# Sheet4.net
KiCad netlist of a schematic drawn in Altium Designer
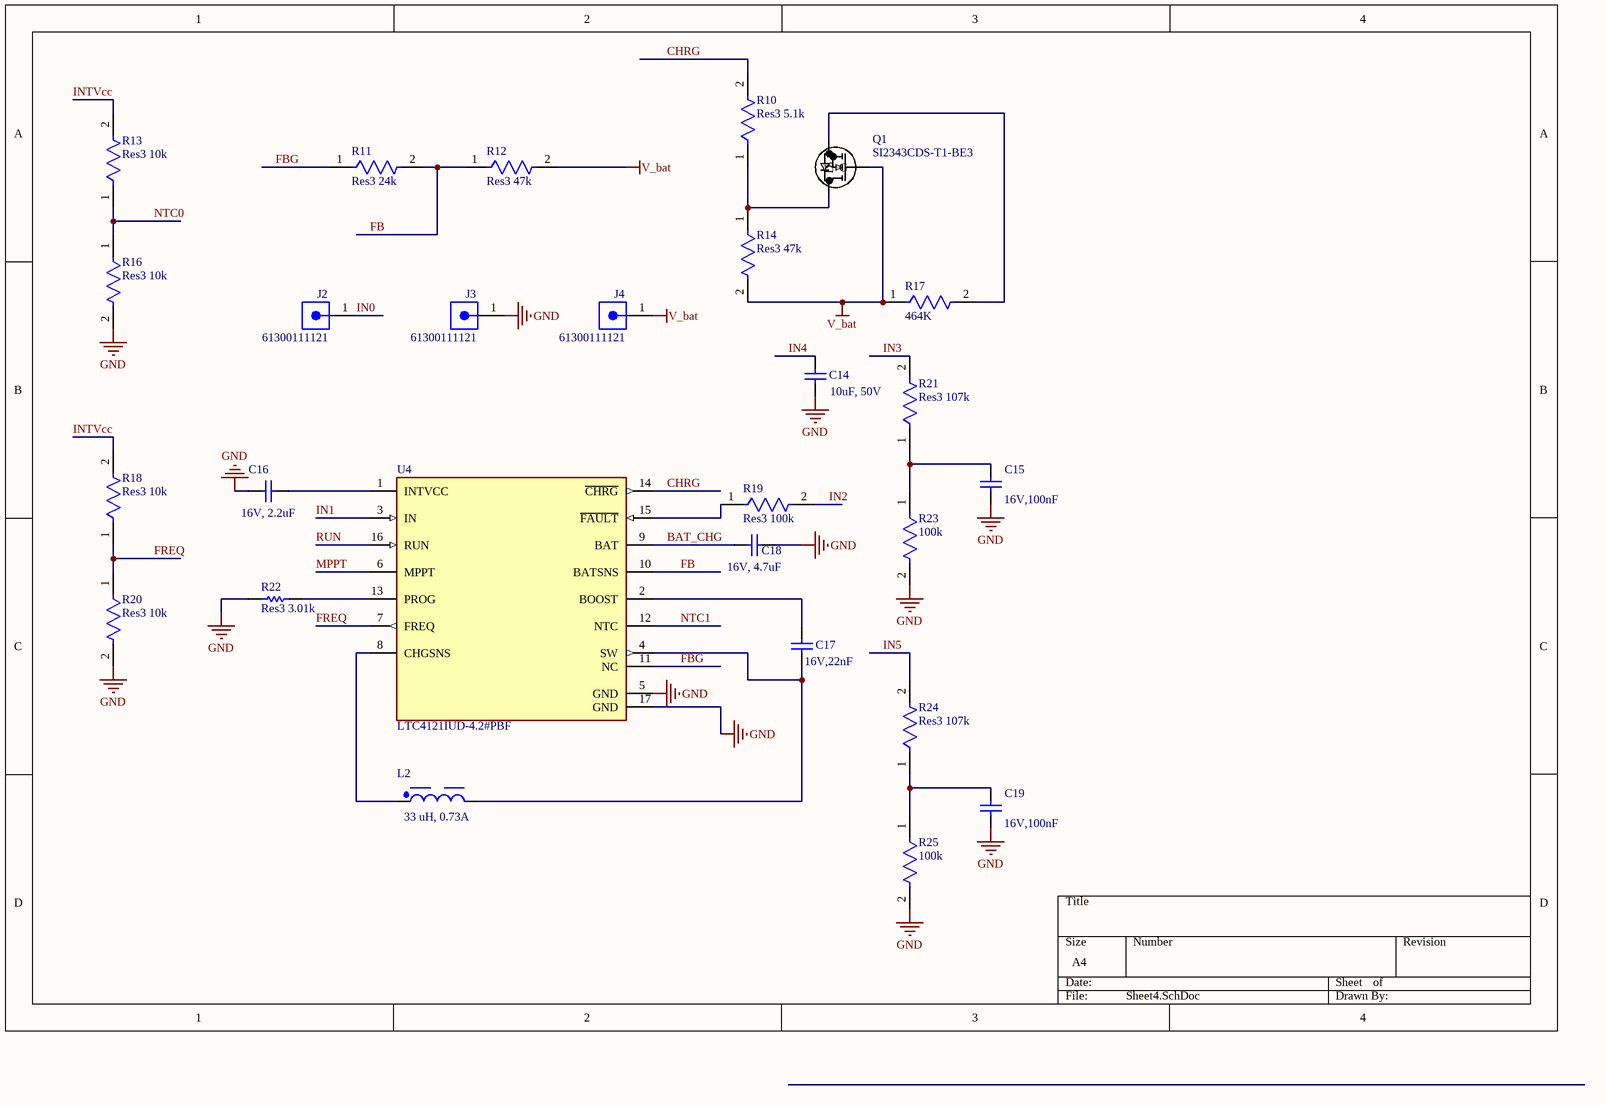
[diagram p0: Sheet4.SchDoc]

(export (version "E")
  (design (tool "Eeschema 10.0.6"))
  (components
    (comp (ref "C14")
      (value "10uF, 50V")
      (footprint "WCAP-CSGP_1206_L3.2W1.6H1.6")
      (description "Cap, 10Uf, 50V, Mlcc, 1206 Rohs Compliant: Yes")
      (libsource (lib "Altium Content Vault") (part "Capacitor_Non-Polarized"))
    )
    (comp (ref "C15")
      (value "16V,100nF")
      (footprint "WCAP-CSGP_0603_L1.6W0.8H0.8_Reflow")
      (description "Cap Ceramic 0.1uF 16V X7R 10% Pad SMD 0603 125C T/R")
      (fields (field (name "TOLERANCE") "10%"))
      (libsource (lib "Altium Content Vault") (part "Capacitor_Non-Polarized"))
    )
    (comp (ref "C16")
      (value "16V, 2.2uF")
      (footprint "WCAP-CSGP_0603_L1.6W0.8H0.8_Reflow")
      (description "Cap Ceramic 2.2uF 16V X5R 20% Pad SMD 0603 85C T/R")
      (fields (field (name "TOLERANCE") "20%"))
      (libsource (lib "Altium Content Vault") (part "Capacitor_Non-Polarized"))
    )
    (comp (ref "C17")
      (value "16V,22nF")
      (footprint "WCAP-CSGP_0603_L1.6W0.8H0.8_Reflow")
      (description "Cap Ceramic 0.022uF 16V X7R 10% Pad SMD 0603 125C T/R")
      (fields (field (name "TOLERANCE") "10%"))
      (libsource (lib "Altium Content Vault") (part "Capacitor_Non-Polarized"))
    )
    (comp (ref "C18")
      (value "16V, 4.7uF")
      (footprint "WCAP-CSGP_0805_L2W1.25H1.25")
      (description "Multilayer Ceramic Capacitor 4.7uF 0805")
      (fields (field (name "TOLERANCE") "20%"))
      (libsource (lib "Altium Content Vault") (part "Capacitor_Non-Polarized"))
    )
    (comp (ref "C19")
      (value "16V,100nF")
      (footprint "WCAP-CSGP_0603_L1.6W0.8H0.8_Reflow")
      (description "Cap Ceramic 0.1uF 16V X7R 10% Pad SMD 0603 125C T/R")
      (fields (field (name "TOLERANCE") "10%"))
      (libsource (lib "Altium Content Vault") (part "Capacitor_Non-Polarized"))
    )
    (comp (ref "J2")
      (value "61300111121")
      (footprint "61300111121")
      (description "THT Vertical Pin Header WR-PHD, Pitch 2.54 mm, Single Row, 1 pins")
      (libsource (lib "Altium Content Vault") (part "Header_Male_1R_01P"))
    )
    (comp (ref "J3")
      (value "61300111121")
      (footprint "61300111121")
      (description "THT Vertical Pin Header WR-PHD, Pitch 2.54 mm, Single Row, 1 pins")
      (libsource (lib "Altium Content Vault") (part "Header_Male_1R_01P"))
    )
    (comp (ref "J4")
      (value "61300111121")
      (footprint "61300111121")
      (description "THT Vertical Pin Header WR-PHD, Pitch 2.54 mm, Single Row, 1 pins")
      (libsource (lib "Altium Content Vault") (part "Header_Male_1R_01P"))
    )
    (comp (ref "L2")
      (value "33 uH, 0.73A")
      (footprint "WE-TPC_4818")
      (description "WE-TPC SMT Shielded Tiny Power Inductor")
      (libsource (lib "Altium Content Vault") (part "Inductor - 2"))
    )
    (comp (ref "Q1")
      (value "SI2343CDS-T1-BE3")
      (footprint "SOT-23_TO-236_VIS")
      (description "P-CHANNEL 30-V (D-S) MOSFET")
      (fields (field (name "COPYRIGHT") "Copyright (C) 2026 Ultra Librarian. All rights reserved."))
      (libsource (lib "Schlib1") (part "SI2343CDS-T1-BE3"))
    )
    (comp (ref "R10")
      (value "Res3 5.1k")
      (footprint "FP-RMCF0603-IPC_A")
      (description "5.1kΩ ±5% 0.1W 0603 Thick Film Chip Resistor AEC-Q200 compliant")
      (fields (field (name "TOLERANCE") "5%"))
      (libsource (lib "Altium Content Vault") (part "1029c3af85768c4190bb7ad29bc67b5"))
    )
    (comp (ref "R11")
      (value "Res3 24k")
      (footprint "FP-CRCW0603-e3-IPC_B")
      (description "RES Thick Film, 24kΩ, 1%, 0.1W, 100ppm/°C, 0603")
      (fields (field (name "TOLERANCE") "1%"))
      (libsource (lib "Altium Content Vault") (part "1029c3af85768c4190bb7ad29bc67b5"))
    )
    (comp (ref "R12")
      (value "Res3 47k")
      (footprint "FP-CRGCQ0603-IPC_C")
      (description "CRGCQ 0603 47K 1%")
      (fields
        (field (name "MANUFACTURER") "TE Connectivity")
        (field (name "MANUFACTURER PART NUMBER") "CRGCQ0603F47K")
      )
      (libsource (lib "Altium Content Vault") (part "1029c3af85768c4190bb7ad29bc67b5"))
    )
    (comp (ref "R13")
      (value "Res3 10k")
      (footprint "FP-SG73P1J-MFG")
      (description "SG73P1JTTD1002F Res Thick Film 0603 10K Ohm 1% 0.2W(1/5W) ±100ppm/C Pad SMD Automotive T/R")
      (fields (field (name "TOLERANCE") "1%"))
      (libsource (lib "Altium Content Vault") (part "1029c3af85768c4190bb7ad29bc67b5"))
    )
    (comp (ref "R14")
      (value "Res3 47k")
      (footprint "FP-CRGCQ0603-IPC_C")
      (description "CRGCQ 0603 47K 1%")
      (fields
        (field (name "MANUFACTURER") "TE Connectivity")
        (field (name "MANUFACTURER PART NUMBER") "CRGCQ0603F47K")
      )
      (libsource (lib "Altium Content Vault") (part "1029c3af85768c4190bb7ad29bc67b5"))
    )
    (comp (ref "R16")
      (value "Res3 10k")
      (footprint "FP-SG73P1J-MFG")
      (description "SG73P1JTTD1002F Res Thick Film 0603 10K Ohm 1% 0.2W(1/5W) ±100ppm/C Pad SMD Automotive T/R")
      (fields (field (name "TOLERANCE") "1%"))
      (libsource (lib "Altium Content Vault") (part "1029c3af85768c4190bb7ad29bc67b5"))
    )
    (comp (ref "R17")
      (value "464K")
      (footprint "FP-CRCW0603-HPe3-IPC_C")
      (description "RES Thick Film, 464kΩ, 1%, 0.33W, 100ppm/°C, 0603")
      (fields (field (name "TOLERANCE") "1%"))
      (libsource (lib "Altium Content Vault") (part "1029c3af85768c4190bb7ad29bc67b5"))
    )
    (comp (ref "R18")
      (value "Res3 10k")
      (footprint "FP-SG73P1J-MFG")
      (description "SG73P1JTTD1002F Res Thick Film 0603 10K Ohm 1% 0.2W(1/5W) ±100ppm/C Pad SMD Automotive T/R")
      (fields (field (name "TOLERANCE") "1%"))
      (libsource (lib "Altium Content Vault") (part "1029c3af85768c4190bb7ad29bc67b5"))
    )
    (comp (ref "R19")
      (value "Res3 100k")
      (footprint "FP-CRGP0603-IPC_C")
      (description "CRGP 0603 100K 1%")
      (fields
        (field (name "MANUFACTURER") "TE")
        (field (name "OCTOPART") "https://octopart.com/crgp0603f100k-te+connectivity-91018719")
      )
      (libsource (lib "Altium Content Vault") (part "1029c3af85768c4190bb7ad29bc67b5"))
    )
    (comp (ref "R20")
      (value "Res3 10k")
      (footprint "FP-SG73P1J-MFG")
      (description "SG73P1JTTD1002F Res Thick Film 0603 10K Ohm 1% 0.2W(1/5W) ±100ppm/C Pad SMD Automotive T/R")
      (fields (field (name "TOLERANCE") "1%"))
      (libsource (lib "Altium Content Vault") (part "1029c3af85768c4190bb7ad29bc67b5"))
    )
    (comp (ref "R21")
      (value "Res3 107k")
      (footprint "FP-CPF0603-MFG")
      (description "RES SMD 107KΩ 0.1% 1/16W 0603")
      (fields
        (field (name "OCTOPART") "https://octopart.com/cpf0603b107ke1-te+connectivity-22739702")
        (field (name "TOLERANCE") "0.1%")
      )
      (libsource (lib "Altium Content Vault") (part "1029c3af85768c4190bb7ad29bc67b5"))
    )
    (comp (ref "R22")
      (value "Res3 3.01k")
      (footprint "RESC1608X55X30ML20T10")
      (fields (field (name "MANUFACTURER") "KOA Speer") (field (name "PART NUMBER") "RK73H1JTTD3011F"))
      (libsource (lib "Altium Content Vault") (part "RES"))
    )
    (comp (ref "R23")
      (value "100k")
      (footprint "FP-CRGP0603-IPC_C")
      (description "CRGP 0603 100K 1%")
      (fields
        (field (name "MANUFACTURER") "TE")
        (field (name "OCTOPART") "https://octopart.com/crgp0603f100k-te+connectivity-91018719")
      )
      (libsource (lib "Altium Content Vault") (part "1029c3af85768c4190bb7ad29bc67b5"))
    )
    (comp (ref "R24")
      (value "Res3 107k")
      (footprint "FP-CPF0603-MFG")
      (description "RES SMD 107KΩ 0.1% 1/16W 0603")
      (fields
        (field (name "OCTOPART") "https://octopart.com/cpf0603b107ke1-te+connectivity-22739702")
        (field (name "TOLERANCE") "0.1%")
      )
      (libsource (lib "Altium Content Vault") (part "1029c3af85768c4190bb7ad29bc67b5"))
    )
    (comp (ref "R25")
      (value "100k")
      (footprint "FP-CRGP0603-IPC_C")
      (description "CRGP 0603 100K 1%")
      (fields
        (field (name "MANUFACTURER") "TE")
        (field (name "OCTOPART") "https://octopart.com/crgp0603f100k-te+connectivity-91018719")
      )
      (libsource (lib "Altium Content Vault") (part "1029c3af85768c4190bb7ad29bc67b5"))
    )
    (comp (ref "U4")
      (value "LTC4121IUD-4.2#PBF")
      (footprint "FP-UD-16-05-08-1691-IPC_B")
      (description "IC BATT CHG LI-ION 16QFN")
      (libsource (lib "Altium Content Vault") (part "3d1be35e09be65839e5aa2a499676d6"))
    )
  )
  (nets
    (net (code "1") (name "/BAT_CHG") (class "Default")
      (node (ref "C18") (pin "1") (pinfunction "1_1") (pintype "passive"))
      (node (ref "U4") (pin "9") (pinfunction "BAT_9") (pintype "power_in"))
    )
    (net (code "2") (name "/CHRG") (class "Default")
      (node (ref "R10") (pin "2") (pinfunction "2_2") (pintype "passive"))
      (node (ref "U4") (pin "14") (pinfunction "~{CHRG}_14") (pintype "output"))
    )
    (net (code "3") (name "/FB") (class "Default")
      (node (ref "R11") (pin "2") (pinfunction "2_2") (pintype "passive"))
      (node (ref "R12") (pin "1") (pinfunction "1_1") (pintype "passive"))
      (node (ref "U4") (pin "10") (pinfunction "BATSNS_10") (pintype "passive"))
    )
    (net (code "4") (name "/FBG") (class "Default")
      (node (ref "R11") (pin "1") (pinfunction "1_1") (pintype "passive"))
      (node (ref "U4") (pin "11") (pinfunction "NC_11") (pintype "passive"))
    )
    (net (code "5") (name "/FREQ") (class "Default")
      (node (ref "R18") (pin "1") (pinfunction "1_1") (pintype "passive"))
      (node (ref "R20") (pin "1") (pinfunction "1_1") (pintype "passive"))
      (node (ref "U4") (pin "7") (pinfunction "FREQ_7") (pintype "output"))
    )
    (net (code "6") (name "/IN0") (class "Default")
      (node (ref "J2") (pin "1") (pinfunction "1_1") (pintype "passive"))
    )
    (net (code "7") (name "/IN1") (class "Default")
      (node (ref "U4") (pin "3") (pinfunction "IN_3") (pintype "input"))
    )
    (net (code "8") (name "/IN2") (class "Default")
      (node (ref "R19") (pin "2") (pinfunction "2_2") (pintype "passive"))
    )
    (net (code "9") (name "/IN3") (class "Default")
      (node (ref "R21") (pin "2") (pinfunction "2_2") (pintype "passive"))
    )
    (net (code "10") (name "/IN4") (class "Default")
      (node (ref "C14") (pin "2") (pinfunction "2_2") (pintype "passive"))
    )
    (net (code "11") (name "/IN5") (class "Default")
      (node (ref "R24") (pin "2") (pinfunction "2_2") (pintype "passive"))
    )
    (net (code "12") (name "/INTVcc") (class "Default")
      (node (ref "R13") (pin "2") (pinfunction "2_2") (pintype "passive"))
      (node (ref "R18") (pin "2") (pinfunction "2_2") (pintype "passive"))
    )
    (net (code "13") (name "/MPPT") (class "Default")
      (node (ref "U4") (pin "6") (pinfunction "MPPT_6") (pintype "passive"))
    )
    (net (code "14") (name "/NTC0") (class "Default")
      (node (ref "R13") (pin "1") (pinfunction "1_1") (pintype "passive"))
      (node (ref "R16") (pin "1") (pinfunction "1_1") (pintype "passive"))
    )
    (net (code "15") (name "/NTC1") (class "Default")
      (node (ref "U4") (pin "12") (pinfunction "NTC_12") (pintype "passive"))
    )
    (net (code "16") (name "/RUN") (class "Default")
      (node (ref "U4") (pin "16") (pinfunction "RUN_16") (pintype "input"))
    )
    (net (code "17") (name "GND") (class "Default")
      (node (ref "C14") (pin "1") (pinfunction "1_1") (pintype "passive"))
      (node (ref "C15") (pin "2") (pinfunction "2_2") (pintype "passive"))
      (node (ref "C16") (pin "1") (pinfunction "1_1") (pintype "passive"))
      (node (ref "C18") (pin "2") (pinfunction "2_2") (pintype "passive"))
      (node (ref "C19") (pin "2") (pinfunction "2_2") (pintype "passive"))
      (node (ref "J3") (pin "1") (pinfunction "1_1") (pintype "passive"))
      (node (ref "R16") (pin "2") (pinfunction "2_2") (pintype "passive"))
      (node (ref "R20") (pin "2") (pinfunction "2_2") (pintype "passive"))
      (node (ref "R22") (pin "1") (pinfunction "1_1") (pintype "passive"))
      (node (ref "R23") (pin "2") (pinfunction "2_2") (pintype "passive"))
      (node (ref "R25") (pin "2") (pinfunction "2_2") (pintype "passive"))
      (node (ref "U4") (pin "17") (pinfunction "GND_17") (pintype "power_in"))
      (node (ref "U4") (pin "5") (pinfunction "GND_5") (pintype "power_in"))
    )
    (net (code "18") (name "Net-(C15-Pad1)") (class "Default")
      (node (ref "C15") (pin "1") (pinfunction "1_1") (pintype "passive"))
      (node (ref "R21") (pin "1") (pinfunction "1_1") (pintype "passive"))
      (node (ref "R23") (pin "1") (pinfunction "1_1") (pintype "passive"))
    )
    (net (code "19") (name "Net-(C19-Pad1)") (class "Default")
      (node (ref "C19") (pin "1") (pinfunction "1_1") (pintype "passive"))
      (node (ref "R24") (pin "1") (pinfunction "1_1") (pintype "passive"))
      (node (ref "R25") (pin "1") (pinfunction "1_1") (pintype "passive"))
    )
    (net (code "20") (name "Net-(Q1-D)") (class "Default")
      (node (ref "Q1") (pin "3") (pinfunction "D_3") (pintype "passive"))
      (node (ref "R10") (pin "1") (pinfunction "1_1") (pintype "passive"))
      (node (ref "R14") (pin "1") (pinfunction "1_1") (pintype "passive"))
    )
    (net (code "21") (name "Net-(Q1-S)") (class "Default")
      (node (ref "Q1") (pin "2") (pinfunction "S_2") (pintype "passive"))
      (node (ref "R17") (pin "2") (pinfunction "2_2") (pintype "passive"))
    )
    (net (code "22") (name "Net-(U4-BOOST)") (class "Default")
      (node (ref "C17") (pin "2") (pinfunction "2_2") (pintype "passive"))
      (node (ref "U4") (pin "2") (pinfunction "BOOST_2") (pintype "passive"))
    )
    (net (code "23") (name "Net-(U4-CHGSNS)") (class "Default")
      (node (ref "L2") (pin "1") (pinfunction "1_1") (pintype "passive"))
      (node (ref "U4") (pin "8") (pinfunction "CHGSNS_8") (pintype "passive"))
    )
    (net (code "24") (name "Net-(U4-INTVCC)") (class "Default")
      (node (ref "C16") (pin "2") (pinfunction "2_2") (pintype "passive"))
      (node (ref "U4") (pin "1") (pinfunction "INTVCC_1") (pintype "power_in"))
    )
    (net (code "25") (name "Net-(U4-PROG)") (class "Default")
      (node (ref "R22") (pin "2") (pinfunction "2_2") (pintype "passive"))
      (node (ref "U4") (pin "13") (pinfunction "PROG_13") (pintype "passive"))
    )
    (net (code "26") (name "Net-(U4-SW)") (class "Default")
      (node (ref "C17") (pin "1") (pinfunction "1_1") (pintype "passive"))
      (node (ref "L2") (pin "2") (pinfunction "2_2") (pintype "passive"))
      (node (ref "U4") (pin "4") (pinfunction "SW_4") (pintype "output"))
    )
    (net (code "27") (name "Net-(U4-~{FAULT})") (class "Default")
      (node (ref "R19") (pin "1") (pinfunction "1_1") (pintype "passive"))
      (node (ref "U4") (pin "15") (pinfunction "~{FAULT}_15") (pintype "input"))
    )
    (net (code "28") (name "V_bat") (class "Default")
      (node (ref "J4") (pin "1") (pinfunction "1_1") (pintype "passive"))
      (node (ref "Q1") (pin "1") (pinfunction "G_1") (pintype "passive"))
      (node (ref "R12") (pin "2") (pinfunction "2_2") (pintype "passive"))
      (node (ref "R14") (pin "2") (pinfunction "2_2") (pintype "passive"))
      (node (ref "R17") (pin "1") (pinfunction "1_1") (pintype "passive"))
    )
  )
)
